# Microhard_DB9_Supply.net
KiCad netlist of a schematic drawn in EAGLE
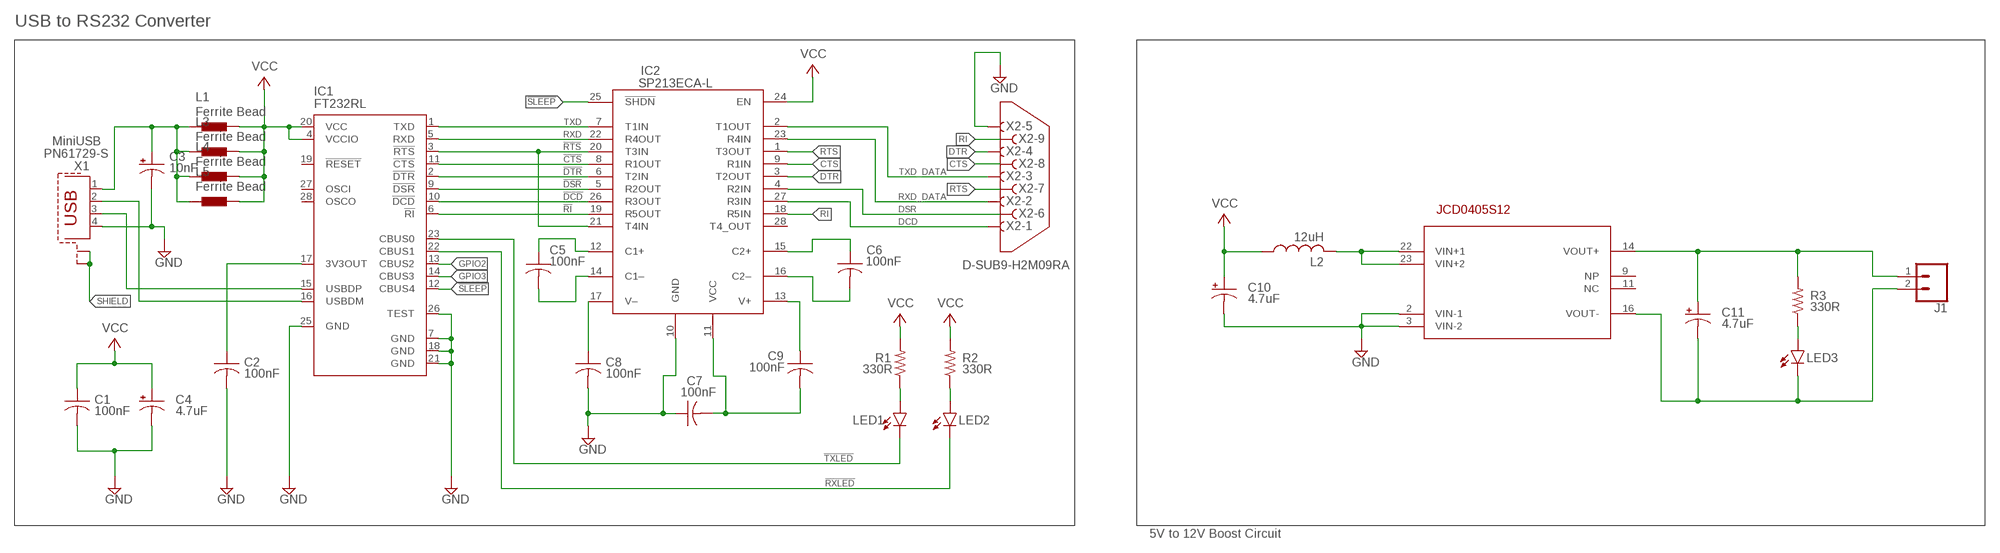
[diagram p0: schematic, sheet 1]

(export (version "E")
  (design (tool "Eeschema 10.0.6"))
  (components
    (comp (ref "C1")
      (value "100nF")
      (footprint "eagle-import:C0402")
      (libsource (lib "eagle-import") (part "C-USC0402"))
    )
    (comp (ref "C2")
      (value "100nF")
      (footprint "eagle-import:C0402")
      (libsource (lib "eagle-import") (part "C-USC0402"))
    )
    (comp (ref "C3")
      (value "10nF")
      (footprint "eagle-import:PANASONIC_A")
      (libsource (lib "eagle-import") (part "CPOL-USA"))
    )
    (comp (ref "C4")
      (value "4.7uF")
      (footprint "eagle-import:PANASONIC_D")
      (libsource (lib "eagle-import") (part "CPOL-USD"))
    )
    (comp (ref "C5")
      (value "100nF")
      (footprint "eagle-import:C0402")
      (libsource (lib "eagle-import") (part "C-USC0402"))
    )
    (comp (ref "C6")
      (value "100nF")
      (footprint "eagle-import:C0402")
      (libsource (lib "eagle-import") (part "C-USC0402"))
    )
    (comp (ref "C7")
      (value "100nF")
      (footprint "eagle-import:C0402")
      (libsource (lib "eagle-import") (part "C-USC0402"))
    )
    (comp (ref "C8")
      (value "100nF")
      (footprint "eagle-import:C0402")
      (libsource (lib "eagle-import") (part "C-USC0402"))
    )
    (comp (ref "C9")
      (value "100nF")
      (footprint "eagle-import:C0402")
      (libsource (lib "eagle-import") (part "C-USC0402"))
    )
    (comp (ref "C10")
      (value "4.7uF")
      (footprint "eagle-import:PANASONIC_D")
      (libsource (lib "eagle-import") (part "CPOL-USD"))
    )
    (comp (ref "C11")
      (value "4.7uF")
      (footprint "eagle-import:PANASONIC_D")
      (libsource (lib "eagle-import") (part "CPOL-USD"))
    )
    (comp (ref "IC1")
      (value "FT232RL")
      (footprint "eagle-import:SSOP28")
      (libsource (lib "eagle-import") (part "FT232RL"))
    )
    (comp (ref "IC2")
      (value "SP213ECA-L")
      (footprint "eagle-import:SSOP28")
      (fields (field (name "MPN") "SP213ECA"))
      (libsource (lib "eagle-import") (part "SP213ECA-L"))
    )
    (comp (ref "J1")
      (value "CONN_02LOCK_LONGPADS")
      (footprint "eagle-import:1X02_LOCK_LONGPADS")
      (libsource (lib "eagle-import") (part "CONN_02LOCK_LONGPADS"))
    )
    (comp (ref "L1")
      (value "Ferrite Bead")
      (footprint "eagle-import:0402")
      (fields (field (name "SPICEPREFIX") "L"))
      (libsource (lib "eagle-import") (part "BLM15HB121SN1"))
    )
    (comp (ref "L2")
      (value "12uH")
      (footprint "eagle-import:0207_7")
      (libsource (lib "eagle-import") (part "L-US0207/7"))
    )
    (comp (ref "L3")
      (value "Ferrite Bead")
      (footprint "eagle-import:0402")
      (fields (field (name "SPICEPREFIX") "L"))
      (libsource (lib "eagle-import") (part "BLM15HB121SN1"))
    )
    (comp (ref "L4")
      (value "Ferrite Bead")
      (footprint "eagle-import:0402")
      (fields (field (name "SPICEPREFIX") "L"))
      (libsource (lib "eagle-import") (part "BLM15HB121SN1"))
    )
    (comp (ref "L5")
      (value "Ferrite Bead")
      (footprint "eagle-import:0402")
      (fields (field (name "SPICEPREFIX") "L"))
      (libsource (lib "eagle-import") (part "BLM15HB121SN1"))
    )
    (comp (ref "LED1")
      (value "LEDCHIP-LED0603")
      (footprint "eagle-import:CHIP-LED0603")
      (libsource (lib "eagle-import") (part "LEDCHIP-LED0603"))
    )
    (comp (ref "LED2")
      (value "LEDCHIP-LED0603")
      (footprint "eagle-import:CHIP-LED0603")
      (libsource (lib "eagle-import") (part "LEDCHIP-LED0603"))
    )
    (comp (ref "LED3")
      (value "LEDCHIP-LED0603")
      (footprint "eagle-import:CHIP-LED0603")
      (libsource (lib "eagle-import") (part "LEDCHIP-LED0603"))
    )
    (comp (ref "R1")
      (value "330R")
      (footprint "eagle-import:R0402")
      (libsource (lib "eagle-import") (part "R-US_R0402"))
    )
    (comp (ref "R2")
      (value "330R")
      (footprint "eagle-import:R0402")
      (libsource (lib "eagle-import") (part "R-US_R0402"))
    )
    (comp (ref "R3")
      (value "330R")
      (footprint "eagle-import:R0402")
      (libsource (lib "eagle-import") (part "R-US_R0402"))
    )
    (comp (ref "U$1")
      (value "JCD0505S12JCD0505S12")
      (footprint "eagle-import:DIP1524W53P254L3175H1040Q24A")
      (libsource (lib "eagle-import") (part "JCD0505S12JCD0505S12"))
    )
    (comp (ref "X1")
      (value "PN61729-S")
      (footprint "eagle-import:PN61729-S")
      (libsource (lib "eagle-import") (part "PN61729-S"))
    )
    (comp (ref "X2")
      (value "D-SUB9-H2M09RA")
      (footprint "eagle-import:H2M09RA")
      (libsource (lib "eagle-import") (part "D-SUB9-H2M09RA"))
    )
  )
  (nets
    (net (code "1") (name "/DCD") (class "Default")
      (node (ref "IC2") (pin "27") (pinfunction "R3IN_27") (pintype "input"))
      (node (ref "X2") (pin "1") (pinfunction "F_1") (pintype "passive"))
    )
    (net (code "2") (name "/DSR") (class "Default")
      (node (ref "IC2") (pin "4") (pinfunction "R2IN_4") (pintype "input"))
      (node (ref "X2") (pin "6") (pinfunction "F_6") (pintype "passive"))
    )
    (net (code "3") (name "/RXD") (class "Default")
      (node (ref "IC1") (pin "5") (pinfunction "RXD_5") (pintype "input"))
      (node (ref "IC2") (pin "22") (pinfunction "R4OUT_22") (pintype "input"))
    )
    (net (code "4") (name "/RXD_DATA") (class "Default")
      (node (ref "IC2") (pin "23") (pinfunction "R4IN_23") (pintype "input"))
      (node (ref "X2") (pin "2") (pinfunction "F_2") (pintype "passive"))
    )
    (net (code "5") (name "/TXD") (class "Default")
      (node (ref "IC1") (pin "1") (pinfunction "TXD_1") (pintype "output"))
      (node (ref "IC2") (pin "7") (pinfunction "T1IN_7") (pintype "input"))
    )
    (net (code "6") (name "/TXD_DATA") (class "Default")
      (node (ref "IC2") (pin "2") (pinfunction "T1OUT_2") (pintype "input"))
      (node (ref "X2") (pin "3") (pinfunction "F_3") (pintype "passive"))
    )
    (net (code "7") (name "/~{CTS}") (class "Default")
      (node (ref "IC1") (pin "11") (pinfunction "~{CTS}_11") (pintype "input"))
      (node (ref "IC2") (pin "8") (pinfunction "R1OUT_8") (pintype "input"))
    )
    (net (code "8") (name "/~{DCD}") (class "Default")
      (node (ref "IC1") (pin "10") (pinfunction "~{DCD}_10") (pintype "input"))
      (node (ref "IC2") (pin "26") (pinfunction "R3OUT_26") (pintype "input"))
    )
    (net (code "9") (name "/~{DSR}") (class "Default")
      (node (ref "IC1") (pin "9") (pinfunction "~{DSR}_9") (pintype "input"))
      (node (ref "IC2") (pin "5") (pinfunction "R2OUT_5") (pintype "input"))
    )
    (net (code "10") (name "/~{DTR}") (class "Default")
      (node (ref "IC1") (pin "2") (pinfunction "~{DTR}_2") (pintype "output"))
      (node (ref "IC2") (pin "6") (pinfunction "T2IN_6") (pintype "input"))
    )
    (net (code "11") (name "/~{RI}") (class "Default")
      (node (ref "IC1") (pin "6") (pinfunction "~{RI}_6") (pintype "input"))
      (node (ref "IC2") (pin "19") (pinfunction "R5OUT_19") (pintype "input"))
    )
    (net (code "12") (name "/~{RTS}") (class "Default")
      (node (ref "IC1") (pin "3") (pinfunction "~{RTS}_3") (pintype "output"))
      (node (ref "IC2") (pin "20") (pinfunction "T3IN_20") (pintype "input"))
      (node (ref "IC2") (pin "21") (pinfunction "T4IN_21") (pintype "input"))
    )
    (net (code "13") (name "/~{RXLED}") (class "Default")
      (node (ref "IC1") (pin "22") (pinfunction "CBUS1_22") (pintype "bidirectional"))
      (node (ref "LED2") (pin "C") (pinfunction "C_C") (pintype "passive"))
    )
    (net (code "14") (name "/~{SLEEP}") (class "Default")
      (node (ref "IC1") (pin "12") (pinfunction "CBUS4_12") (pintype "bidirectional"))
      (node (ref "IC2") (pin "25") (pinfunction "~{SHDN}_25") (pintype "input"))
    )
    (net (code "15") (name "/~{TXLED}") (class "Default")
      (node (ref "IC1") (pin "23") (pinfunction "CBUS0_23") (pintype "bidirectional"))
      (node (ref "LED1") (pin "C") (pinfunction "C_C") (pintype "passive"))
    )
    (net (code "16") (name "CTS") (class "Default")
      (node (ref "IC2") (pin "9") (pinfunction "R1IN_9") (pintype "input"))
      (node (ref "X2") (pin "8") (pinfunction "F_8") (pintype "passive"))
    )
    (net (code "17") (name "DTR") (class "Default")
      (node (ref "IC2") (pin "3") (pinfunction "T2OUT_3") (pintype "input"))
      (node (ref "X2") (pin "4") (pinfunction "F_4") (pintype "passive"))
    )
    (net (code "18") (name "GND") (class "Default")
      (node (ref "C1") (pin "2") (pinfunction "2_2") (pintype "passive"))
      (node (ref "C10") (pin "-") (pinfunction "-_-") (pintype "passive"))
      (node (ref "C2") (pin "2") (pinfunction "2_2") (pintype "passive"))
      (node (ref "C3") (pin "-") (pinfunction "-_-") (pintype "passive"))
      (node (ref "C4") (pin "-") (pinfunction "-_-") (pintype "passive"))
      (node (ref "C7") (pin "1") (pinfunction "1_1") (pintype "passive"))
      (node (ref "C8") (pin "2") (pinfunction "2_2") (pintype "passive"))
      (node (ref "IC1") (pin "18") (pinfunction "GND_18") (pintype "power_in"))
      (node (ref "IC1") (pin "21") (pinfunction "GND_21") (pintype "power_in"))
      (node (ref "IC1") (pin "25") (pinfunction "GND_25") (pintype "power_in"))
      (node (ref "IC1") (pin "26") (pinfunction "TEST_26") (pintype "input"))
      (node (ref "IC1") (pin "7") (pinfunction "GND_7") (pintype "power_in"))
      (node (ref "IC2") (pin "10") (pinfunction "GND_10") (pintype "input"))
      (node (ref "U$1") (pin "2") (pinfunction "VIN-1_2") (pintype "bidirectional"))
      (node (ref "U$1") (pin "3") (pinfunction "VIN-2_3") (pintype "bidirectional"))
      (node (ref "X1") (pin "4") (pinfunction "4_4") (pintype "passive"))
      (node (ref "X2") (pin "5") (pinfunction "F_5") (pintype "passive"))
    )
    (net (code "19") (name "GPIO2") (class "Default")
      (node (ref "IC1") (pin "13") (pinfunction "CBUS2_13") (pintype "bidirectional"))
    )
    (net (code "20") (name "GPIO3") (class "Default")
      (node (ref "IC1") (pin "14") (pinfunction "CBUS3_14") (pintype "bidirectional"))
    )
    (net (code "21") (name "Net-(C3-Pad+)") (class "Default")
      (node (ref "C3") (pin "+") (pinfunction "+_+") (pintype "passive"))
      (node (ref "L1") (pin "1") (pinfunction "1_1") (pintype "passive"))
      (node (ref "L3") (pin "1") (pinfunction "1_1") (pintype "passive"))
      (node (ref "L4") (pin "1") (pinfunction "1_1") (pintype "passive"))
      (node (ref "L5") (pin "1") (pinfunction "1_1") (pintype "passive"))
      (node (ref "X1") (pin "1") (pinfunction "1_1") (pintype "passive"))
    )
    (net (code "22") (name "Net-(IC1-3V3OUT)") (class "Default")
      (node (ref "C2") (pin "1") (pinfunction "1_1") (pintype "passive"))
      (node (ref "IC1") (pin "17") (pinfunction "3V3OUT_17") (pintype "output"))
    )
    (net (code "23") (name "Net-(IC1-USBDM)") (class "Default")
      (node (ref "IC1") (pin "16") (pinfunction "USBDM_16") (pintype "bidirectional"))
      (node (ref "X1") (pin "2") (pinfunction "2_2") (pintype "passive"))
    )
    (net (code "24") (name "Net-(IC1-USBDP)") (class "Default")
      (node (ref "IC1") (pin "15") (pinfunction "USBDP_15") (pintype "bidirectional"))
      (node (ref "X1") (pin "3") (pinfunction "3_3") (pintype "passive"))
    )
    (net (code "25") (name "Net-(IC2-C1+)") (class "Default")
      (node (ref "C5") (pin "1") (pinfunction "1_1") (pintype "passive"))
      (node (ref "IC2") (pin "12") (pinfunction "C1+_12") (pintype "input"))
    )
    (net (code "26") (name "Net-(IC2-C1–)") (class "Default")
      (node (ref "C5") (pin "2") (pinfunction "2_2") (pintype "passive"))
      (node (ref "IC2") (pin "14") (pinfunction "C1–_14") (pintype "input"))
    )
    (net (code "27") (name "Net-(IC2-C2+)") (class "Default")
      (node (ref "C6") (pin "1") (pinfunction "1_1") (pintype "passive"))
      (node (ref "IC2") (pin "15") (pinfunction "C2+_15") (pintype "input"))
    )
    (net (code "28") (name "Net-(IC2-C2–)") (class "Default")
      (node (ref "C6") (pin "2") (pinfunction "2_2") (pintype "passive"))
      (node (ref "IC2") (pin "16") (pinfunction "C2–_16") (pintype "input"))
    )
    (net (code "29") (name "Net-(IC2-V+)") (class "Default")
      (node (ref "C9") (pin "1") (pinfunction "1_1") (pintype "passive"))
      (node (ref "IC2") (pin "13") (pinfunction "V+_13") (pintype "input"))
    )
    (net (code "30") (name "Net-(IC2-VCC)") (class "Default")
      (node (ref "C7") (pin "2") (pinfunction "2_2") (pintype "passive"))
      (node (ref "C9") (pin "2") (pinfunction "2_2") (pintype "passive"))
      (node (ref "IC2") (pin "11") (pinfunction "VCC_11") (pintype "input"))
    )
    (net (code "31") (name "Net-(IC2-V–)") (class "Default")
      (node (ref "C8") (pin "1") (pinfunction "1_1") (pintype "passive"))
      (node (ref "IC2") (pin "17") (pinfunction "V–_17") (pintype "input"))
    )
    (net (code "32") (name "Net-(LED1-PadA)") (class "Default")
      (node (ref "LED1") (pin "A") (pinfunction "A_A") (pintype "passive"))
      (node (ref "R1") (pin "1") (pinfunction "1_1") (pintype "passive"))
    )
    (net (code "33") (name "Net-(LED2-PadA)") (class "Default")
      (node (ref "LED2") (pin "A") (pinfunction "A_A") (pintype "passive"))
      (node (ref "R2") (pin "1") (pinfunction "1_1") (pintype "passive"))
    )
    (net (code "34") (name "Net-(LED3-PadA)") (class "Default")
      (node (ref "LED3") (pin "A") (pinfunction "A_A") (pintype "passive"))
      (node (ref "R3") (pin "1") (pinfunction "1_1") (pintype "passive"))
    )
    (net (code "35") (name "Net-(U$1-VIN+1)") (class "Default")
      (node (ref "L2") (pin "2") (pinfunction "2_2") (pintype "passive"))
      (node (ref "U$1") (pin "22") (pinfunction "VIN+1_22") (pintype "bidirectional"))
      (node (ref "U$1") (pin "23") (pinfunction "VIN+2_23") (pintype "bidirectional"))
    )
    (net (code "36") (name "Net-(U$1-VOUT+)") (class "Default")
      (node (ref "C11") (pin "+") (pinfunction "+_+") (pintype "passive"))
      (node (ref "J1") (pin "1") (pinfunction "1_1") (pintype "passive"))
      (node (ref "R3") (pin "2") (pinfunction "2_2") (pintype "passive"))
      (node (ref "U$1") (pin "14") (pinfunction "VOUT+_14") (pintype "bidirectional"))
    )
    (net (code "37") (name "Net-(U$1-VOUT-)") (class "Default")
      (node (ref "C11") (pin "-") (pinfunction "-_-") (pintype "passive"))
      (node (ref "J1") (pin "2") (pinfunction "2_2") (pintype "passive"))
      (node (ref "LED3") (pin "C") (pinfunction "C_C") (pintype "passive"))
      (node (ref "U$1") (pin "16") (pinfunction "VOUT-_16") (pintype "bidirectional"))
    )
    (net (code "38") (name "RI") (class "Default")
      (node (ref "IC2") (pin "18") (pinfunction "R5IN_18") (pintype "input"))
      (node (ref "X2") (pin "9") (pinfunction "F_9") (pintype "passive"))
    )
    (net (code "39") (name "RTS") (class "Default")
      (node (ref "IC2") (pin "1") (pinfunction "T3OUT_1") (pintype "input"))
      (node (ref "X2") (pin "7") (pinfunction "F_7") (pintype "passive"))
    )
    (net (code "40") (name "SHIELD") (class "Default")
      (node (ref "X1") (pin "S1") (pinfunction "S1_S1") (pintype "passive"))
      (node (ref "X1") (pin "S2") (pinfunction "S2_S2") (pintype "passive"))
    )
    (net (code "41") (name "VCC") (class "Default")
      (node (ref "C1") (pin "1") (pinfunction "1_1") (pintype "passive"))
      (node (ref "C10") (pin "+") (pinfunction "+_+") (pintype "passive"))
      (node (ref "C4") (pin "+") (pinfunction "+_+") (pintype "passive"))
      (node (ref "IC1") (pin "20") (pinfunction "VCC_20") (pintype "power_in"))
      (node (ref "IC1") (pin "4") (pinfunction "VCCIO_4") (pintype "power_in"))
      (node (ref "IC2") (pin "24") (pinfunction "EN_24") (pintype "input"))
      (node (ref "L1") (pin "2") (pinfunction "2_2") (pintype "passive"))
      (node (ref "L2") (pin "1") (pinfunction "1_1") (pintype "passive"))
      (node (ref "L3") (pin "2") (pinfunction "2_2") (pintype "passive"))
      (node (ref "L4") (pin "2") (pinfunction "2_2") (pintype "passive"))
      (node (ref "L5") (pin "2") (pinfunction "2_2") (pintype "passive"))
      (node (ref "R1") (pin "2") (pinfunction "2_2") (pintype "passive"))
      (node (ref "R2") (pin "2") (pinfunction "2_2") (pintype "passive"))
    )
    (net (code "42") (name "unconnected-(IC1-OSCI-Pad27)") (class "Default")
      (node (ref "IC1") (pin "27") (pinfunction "OSCI_27") (pintype "input"))
    )
    (net (code "43") (name "unconnected-(IC1-OSCO-Pad28)") (class "Default")
      (node (ref "IC1") (pin "28") (pinfunction "OSCO_28") (pintype "output"))
    )
    (net (code "44") (name "unconnected-(IC1-~{RESET}-Pad19)") (class "Default")
      (node (ref "IC1") (pin "19") (pinfunction "~{RESET}_19") (pintype "input"))
    )
    (net (code "45") (name "unconnected-(IC2-T4_OUT-Pad28)") (class "Default")
      (node (ref "IC2") (pin "28") (pinfunction "T4_OUT_28") (pintype "input"))
    )
    (net (code "46") (name "unconnected-(U$1-NC-Pad11)") (class "Default")
      (node (ref "U$1") (pin "11") (pinfunction "NC_11") (pintype "bidirectional"))
    )
    (net (code "47") (name "unconnected-(U$1-NP-Pad9)") (class "Default")
      (node (ref "U$1") (pin "9") (pinfunction "NP_9") (pintype "bidirectional"))
    )
  )
)
